# sch_design.net
KiCad netlist of a schematic drawn in EAGLE
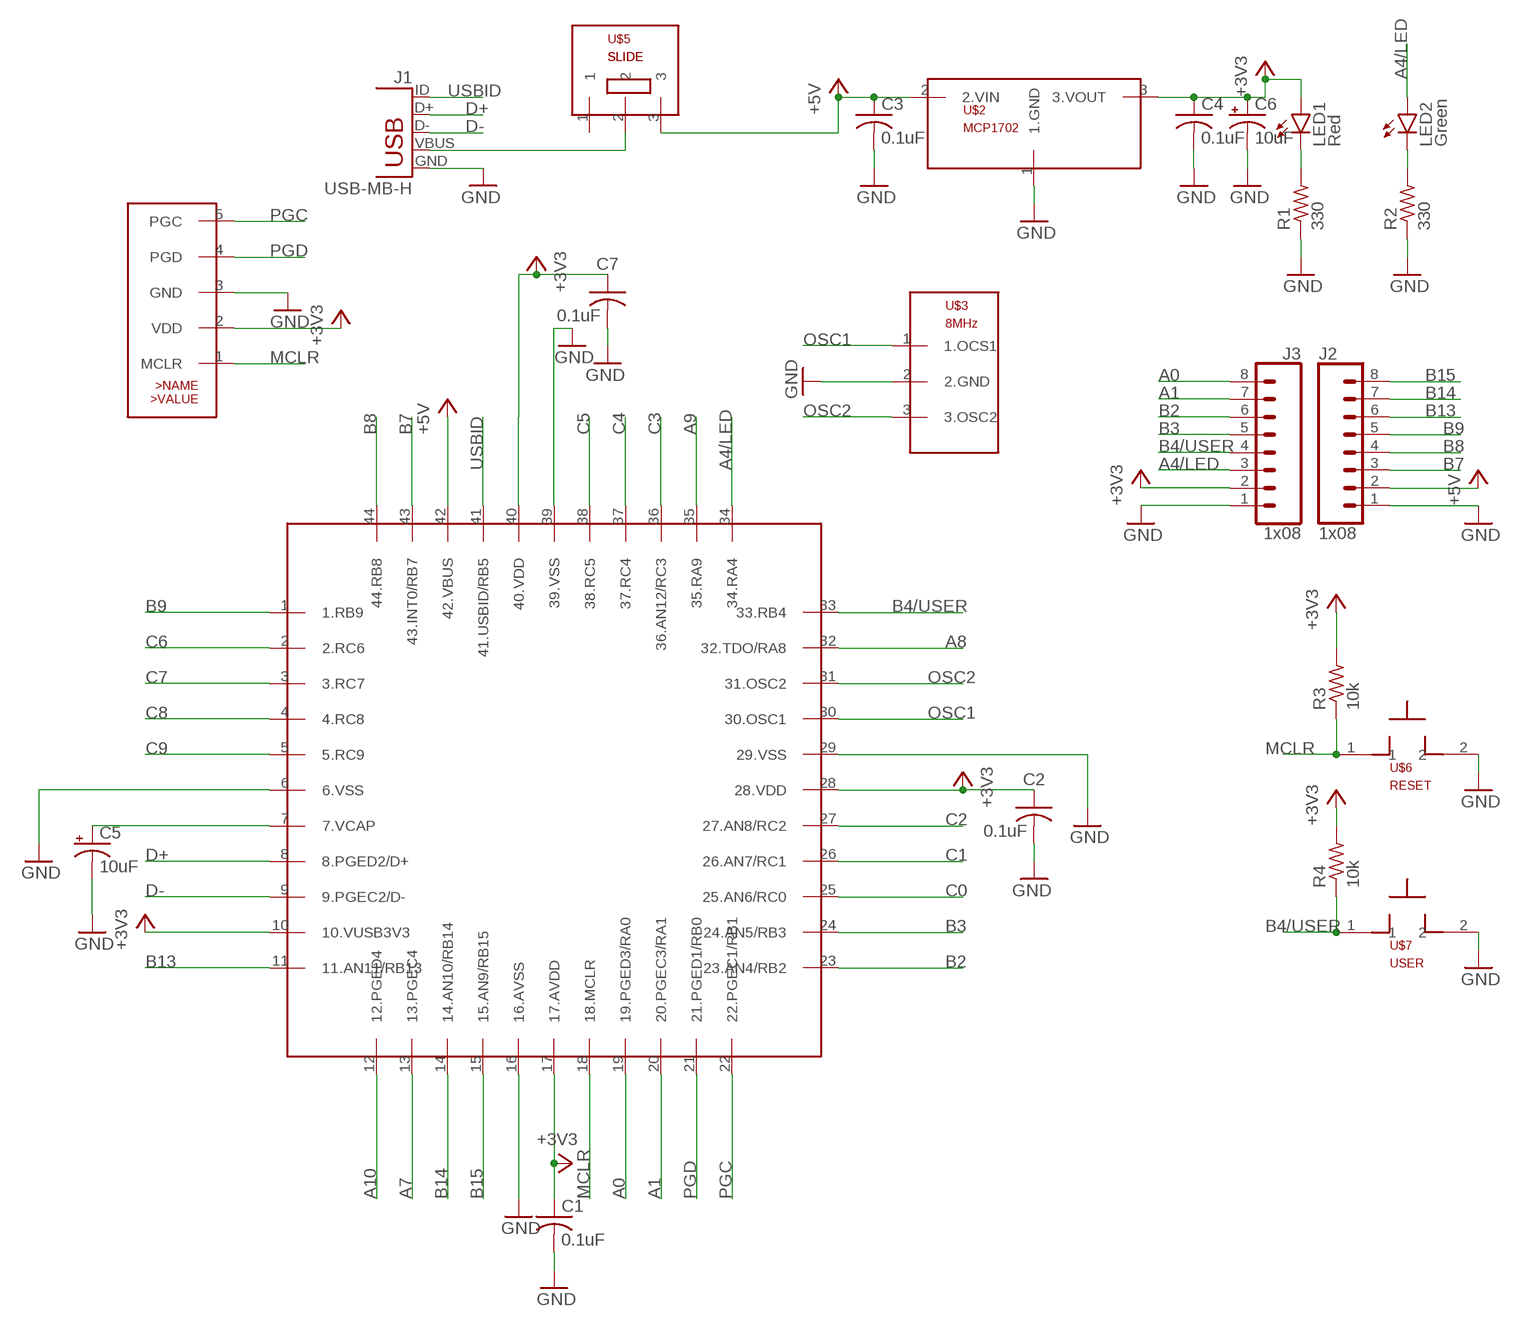
[diagram p0: schematic, sheet 1]

(export (version "E")
  (design (tool "Eeschema 10.0.6"))
  (components
    (comp (ref "C1")
      (value "0.1uF")
      (footprint "eagle-import:C025-025X050")
      (libsource (lib "eagle-import") (part "C-US025-025X050"))
    )
    (comp (ref "C2")
      (value "0.1uF")
      (footprint "eagle-import:C025-025X050")
      (libsource (lib "eagle-import") (part "C-US025-025X050"))
    )
    (comp (ref "C3")
      (value "0.1uF")
      (footprint "eagle-import:C025-025X050")
      (libsource (lib "eagle-import") (part "C-US025-025X050"))
    )
    (comp (ref "C4")
      (value "0.1uF")
      (footprint "eagle-import:C025-025X050")
      (libsource (lib "eagle-import") (part "C-US025-025X050"))
    )
    (comp (ref "C5")
      (value "10uF")
      (footprint "eagle-import:B45181B")
      (libsource (lib "eagle-import") (part "CPOL-USB45181B"))
    )
    (comp (ref "C6")
      (value "10uF")
      (footprint "eagle-import:B45181B")
      (libsource (lib "eagle-import") (part "CPOL-USB45181B"))
    )
    (comp (ref "C7")
      (value "0.1uF")
      (footprint "eagle-import:C025-025X050")
      (libsource (lib "eagle-import") (part "C-US025-025X050"))
    )
    (comp (ref "J1")
      (value "USB-MB-H")
      (footprint "eagle-import:USB-MB-H")
      (libsource (lib "eagle-import") (part "USB-MB-H"))
    )
    (comp (ref "J2")
      (value "1x08")
      (footprint "eagle-import:1X08")
      (libsource (lib "eagle-import") (part "CONN_08{dblquote}"))
    )
    (comp (ref "J3")
      (value "1x08")
      (footprint "eagle-import:1X08")
      (libsource (lib "eagle-import") (part "CONN_08{dblquote}"))
    )
    (comp (ref "LED1")
      (value "Red")
      (footprint "eagle-import:LED3MM")
      (libsource (lib "eagle-import") (part "LED3MM"))
    )
    (comp (ref "LED2")
      (value "Green")
      (footprint "eagle-import:LED3MM")
      (libsource (lib "eagle-import") (part "LED3MM"))
    )
    (comp (ref "R1")
      (value "330")
      (footprint "eagle-import:0207_10")
      (libsource (lib "eagle-import") (part "R-US_0207/10"))
    )
    (comp (ref "R2")
      (value "330")
      (footprint "eagle-import:0207_10")
      (libsource (lib "eagle-import") (part "R-US_0207/10"))
    )
    (comp (ref "R3")
      (value "10k")
      (footprint "eagle-import:0207_10")
      (libsource (lib "eagle-import") (part "R-US_0207/10"))
    )
    (comp (ref "R4")
      (value "10k")
      (footprint "eagle-import:0207_10")
      (libsource (lib "eagle-import") (part "R-US_0207/10"))
    )
    (comp (ref "U$2")
      (value "MCP1702")
      (footprint "eagle-import:TO92")
      (libsource (lib "eagle-import") (part "MCP1702"))
    )
    (comp (ref "U$3")
      (value "8MHz")
      (footprint "eagle-import:OSC")
      (libsource (lib "eagle-import") (part "OSC"))
    )
    (comp (ref "U$4")
      (value "PICKIT3")
      (footprint "eagle-import:1X05")
      (libsource (lib "eagle-import") (part "PICKIT3"))
    )
    (comp (ref "U$5")
      (value "SLIDE")
      (footprint "eagle-import:SLIDE")
      (libsource (lib "eagle-import") (part "SLIDE"))
    )
    (comp (ref "U$6")
      (value "RESET")
      (footprint "eagle-import:PB")
      (libsource (lib "eagle-import") (part "PB"))
    )
    (comp (ref "U$7")
      (value "USER")
      (footprint "eagle-import:PB")
      (libsource (lib "eagle-import") (part "PB"))
    )
    (comp (ref "U$8")
      (value "PIC32MX270F256D")
      (footprint "eagle-import:TQFP44")
      (libsource (lib "eagle-import") (part "PIC32MX270F256D"))
    )
  )
  (nets
    (net (code "1") (name "+3V3") (class "Default")
      (node (ref "C1") (pin "1") (pinfunction "1_1") (pintype "passive"))
      (node (ref "C2") (pin "1") (pinfunction "1_1") (pintype "passive"))
      (node (ref "C4") (pin "1") (pinfunction "1_1") (pintype "passive"))
      (node (ref "C6") (pin "+") (pinfunction "+_+") (pintype "passive"))
      (node (ref "C7") (pin "1") (pinfunction "1_1") (pintype "passive"))
      (node (ref "J3") (pin "2") (pinfunction "2_2") (pintype "passive"))
      (node (ref "LED1") (pin "A") (pinfunction "A_A") (pintype "passive"))
      (node (ref "R3") (pin "2") (pinfunction "2_2") (pintype "passive"))
      (node (ref "R4") (pin "2") (pinfunction "2_2") (pintype "passive"))
      (node (ref "U$2") (pin "3") (pinfunction "3.VOUT_3") (pintype "bidirectional"))
      (node (ref "U$4") (pin "2") (pinfunction "VDD_2") (pintype "bidirectional"))
      (node (ref "U$8") (pin "10") (pinfunction "10.VUSB3V3_10") (pintype "bidirectional"))
      (node (ref "U$8") (pin "17") (pinfunction "17.AVDD_17") (pintype "bidirectional"))
      (node (ref "U$8") (pin "28") (pinfunction "28.VDD_28") (pintype "bidirectional"))
      (node (ref "U$8") (pin "40") (pinfunction "40.VDD_40") (pintype "bidirectional"))
    )
    (net (code "2") (name "+5V") (class "Default")
      (node (ref "C3") (pin "1") (pinfunction "1_1") (pintype "passive"))
      (node (ref "J2") (pin "2") (pinfunction "2_2") (pintype "passive"))
      (node (ref "U$2") (pin "2") (pinfunction "2.VIN_2") (pintype "bidirectional"))
      (node (ref "U$5") (pin "3") (pinfunction "3_3") (pintype "bidirectional"))
      (node (ref "U$8") (pin "42") (pinfunction "42.VBUS_42") (pintype "bidirectional"))
    )
    (net (code "3") (name "/A0") (class "Default")
      (node (ref "J3") (pin "8") (pinfunction "8_8") (pintype "passive"))
      (node (ref "U$8") (pin "19") (pinfunction "19.PGED3/RA0_19") (pintype "bidirectional"))
    )
    (net (code "4") (name "/A1") (class "Default")
      (node (ref "J3") (pin "7") (pinfunction "7_7") (pintype "passive"))
      (node (ref "U$8") (pin "20") (pinfunction "20.PGEC3/RA1_20") (pintype "bidirectional"))
    )
    (net (code "5") (name "/A4{slash}LED") (class "Default")
      (node (ref "J3") (pin "3") (pinfunction "3_3") (pintype "passive"))
      (node (ref "LED2") (pin "A") (pinfunction "A_A") (pintype "passive"))
      (node (ref "U$8") (pin "34") (pinfunction "34.RA4_34") (pintype "bidirectional"))
    )
    (net (code "6") (name "/A7") (class "Default")
      (node (ref "U$8") (pin "13") (pinfunction "13.PGEC4_13") (pintype "bidirectional"))
    )
    (net (code "7") (name "/A8") (class "Default")
      (node (ref "U$8") (pin "32") (pinfunction "32.TDO/RA8_32") (pintype "bidirectional"))
    )
    (net (code "8") (name "/A9") (class "Default")
      (node (ref "U$8") (pin "35") (pinfunction "35.RA9_35") (pintype "bidirectional"))
    )
    (net (code "9") (name "/A10") (class "Default")
      (node (ref "U$8") (pin "12") (pinfunction "12.PGED4_12") (pintype "bidirectional"))
    )
    (net (code "10") (name "/B2") (class "Default")
      (node (ref "J3") (pin "6") (pinfunction "6_6") (pintype "passive"))
      (node (ref "U$8") (pin "23") (pinfunction "23.AN4/RB2_23") (pintype "bidirectional"))
    )
    (net (code "11") (name "/B3") (class "Default")
      (node (ref "J3") (pin "5") (pinfunction "5_5") (pintype "passive"))
      (node (ref "U$8") (pin "24") (pinfunction "24.AN5/RB3_24") (pintype "bidirectional"))
    )
    (net (code "12") (name "/B4{slash}USER") (class "Default")
      (node (ref "J3") (pin "4") (pinfunction "4_4") (pintype "passive"))
      (node (ref "R4") (pin "1") (pinfunction "1_1") (pintype "passive"))
      (node (ref "U$7") (pin "1") (pinfunction "1_1") (pintype "bidirectional"))
      (node (ref "U$8") (pin "33") (pinfunction "33.RB4_33") (pintype "bidirectional"))
    )
    (net (code "13") (name "/B7") (class "Default")
      (node (ref "J2") (pin "3") (pinfunction "3_3") (pintype "passive"))
      (node (ref "U$8") (pin "43") (pinfunction "43.INT0/RB7_43") (pintype "bidirectional"))
    )
    (net (code "14") (name "/B8") (class "Default")
      (node (ref "J2") (pin "4") (pinfunction "4_4") (pintype "passive"))
      (node (ref "U$8") (pin "44") (pinfunction "44.RB8_44") (pintype "bidirectional"))
    )
    (net (code "15") (name "/B9") (class "Default")
      (node (ref "J2") (pin "5") (pinfunction "5_5") (pintype "passive"))
      (node (ref "U$8") (pin "1") (pinfunction "1.RB9_1") (pintype "bidirectional"))
    )
    (net (code "16") (name "/B13") (class "Default")
      (node (ref "J2") (pin "6") (pinfunction "6_6") (pintype "passive"))
      (node (ref "U$8") (pin "11") (pinfunction "11.AN11/RB13_11") (pintype "bidirectional"))
    )
    (net (code "17") (name "/B14") (class "Default")
      (node (ref "J2") (pin "7") (pinfunction "7_7") (pintype "passive"))
      (node (ref "U$8") (pin "14") (pinfunction "14.AN10/RB14_14") (pintype "bidirectional"))
    )
    (net (code "18") (name "/B15") (class "Default")
      (node (ref "J2") (pin "8") (pinfunction "8_8") (pintype "passive"))
      (node (ref "U$8") (pin "15") (pinfunction "15.AN9/RB15_15") (pintype "bidirectional"))
    )
    (net (code "19") (name "/C0") (class "Default")
      (node (ref "U$8") (pin "25") (pinfunction "25.AN6/RC0_25") (pintype "bidirectional"))
    )
    (net (code "20") (name "/C1") (class "Default")
      (node (ref "U$8") (pin "26") (pinfunction "26.AN7/RC1_26") (pintype "bidirectional"))
    )
    (net (code "21") (name "/C2") (class "Default")
      (node (ref "U$8") (pin "27") (pinfunction "27.AN8/RC2_27") (pintype "bidirectional"))
    )
    (net (code "22") (name "/C3") (class "Default")
      (node (ref "U$8") (pin "36") (pinfunction "36.AN12/RC3_36") (pintype "bidirectional"))
    )
    (net (code "23") (name "/C4") (class "Default")
      (node (ref "U$8") (pin "37") (pinfunction "37.RC4_37") (pintype "bidirectional"))
    )
    (net (code "24") (name "/C5") (class "Default")
      (node (ref "U$8") (pin "38") (pinfunction "38.RC5_38") (pintype "bidirectional"))
    )
    (net (code "25") (name "/C6") (class "Default")
      (node (ref "U$8") (pin "2") (pinfunction "2.RC6_2") (pintype "bidirectional"))
    )
    (net (code "26") (name "/C7") (class "Default")
      (node (ref "U$8") (pin "3") (pinfunction "3.RC7_3") (pintype "bidirectional"))
    )
    (net (code "27") (name "/C8") (class "Default")
      (node (ref "U$8") (pin "4") (pinfunction "4.RC8_4") (pintype "bidirectional"))
    )
    (net (code "28") (name "/C9") (class "Default")
      (node (ref "U$8") (pin "5") (pinfunction "5.RC9_5") (pintype "bidirectional"))
    )
    (net (code "29") (name "/D+") (class "Default")
      (node (ref "J1") (pin "D+") (pinfunction "D+_D+") (pintype "bidirectional"))
      (node (ref "U$8") (pin "8") (pinfunction "8.PGED2/D+_8") (pintype "bidirectional"))
    )
    (net (code "30") (name "/D-") (class "Default")
      (node (ref "J1") (pin "D-") (pinfunction "D-_D-") (pintype "bidirectional"))
      (node (ref "U$8") (pin "9") (pinfunction "9.PGEC2/D-_9") (pintype "bidirectional"))
    )
    (net (code "31") (name "/MCLR") (class "Default")
      (node (ref "R3") (pin "1") (pinfunction "1_1") (pintype "passive"))
      (node (ref "U$4") (pin "1") (pinfunction "MCLR_1") (pintype "bidirectional"))
      (node (ref "U$6") (pin "1") (pinfunction "1_1") (pintype "bidirectional"))
      (node (ref "U$8") (pin "18") (pinfunction "18.MCLR_18") (pintype "bidirectional"))
    )
    (net (code "32") (name "/OSC1") (class "Default")
      (node (ref "U$3") (pin "1") (pinfunction "1.OCS1_1") (pintype "bidirectional"))
      (node (ref "U$8") (pin "30") (pinfunction "30.OSC1_30") (pintype "bidirectional"))
    )
    (net (code "33") (name "/OSC2") (class "Default")
      (node (ref "U$3") (pin "3") (pinfunction "3.OSC2_3") (pintype "bidirectional"))
      (node (ref "U$8") (pin "31") (pinfunction "31.OSC2_31") (pintype "bidirectional"))
    )
    (net (code "34") (name "/PGC") (class "Default")
      (node (ref "U$4") (pin "5") (pinfunction "PGC_5") (pintype "bidirectional"))
      (node (ref "U$8") (pin "22") (pinfunction "22.PGEC1/RB1_22") (pintype "bidirectional"))
    )
    (net (code "35") (name "/PGD") (class "Default")
      (node (ref "U$4") (pin "4") (pinfunction "PGD_4") (pintype "bidirectional"))
      (node (ref "U$8") (pin "21") (pinfunction "21.PGED1/RB0_21") (pintype "bidirectional"))
    )
    (net (code "36") (name "/USBID") (class "Default")
      (node (ref "J1") (pin "ID") (pinfunction "ID_ID") (pintype "bidirectional"))
      (node (ref "U$8") (pin "41") (pinfunction "41.USBID/RB5_41") (pintype "bidirectional"))
    )
    (net (code "37") (name "GND") (class "Default")
      (node (ref "C1") (pin "2") (pinfunction "2_2") (pintype "passive"))
      (node (ref "C2") (pin "2") (pinfunction "2_2") (pintype "passive"))
      (node (ref "C3") (pin "2") (pinfunction "2_2") (pintype "passive"))
      (node (ref "C4") (pin "2") (pinfunction "2_2") (pintype "passive"))
      (node (ref "C5") (pin "-") (pinfunction "-_-") (pintype "passive"))
      (node (ref "C6") (pin "-") (pinfunction "-_-") (pintype "passive"))
      (node (ref "C7") (pin "2") (pinfunction "2_2") (pintype "passive"))
      (node (ref "J1") (pin "GND") (pinfunction "GND_GND") (pintype "bidirectional"))
      (node (ref "J2") (pin "1") (pinfunction "1_1") (pintype "passive"))
      (node (ref "J3") (pin "1") (pinfunction "1_1") (pintype "passive"))
      (node (ref "R1") (pin "1") (pinfunction "1_1") (pintype "passive"))
      (node (ref "R2") (pin "1") (pinfunction "1_1") (pintype "passive"))
      (node (ref "U$2") (pin "1") (pinfunction "1.GND_1") (pintype "bidirectional"))
      (node (ref "U$3") (pin "2") (pinfunction "2.GND_2") (pintype "bidirectional"))
      (node (ref "U$4") (pin "3") (pinfunction "GND_3") (pintype "bidirectional"))
      (node (ref "U$6") (pin "2") (pinfunction "2_2") (pintype "bidirectional"))
      (node (ref "U$7") (pin "2") (pinfunction "2_2") (pintype "bidirectional"))
      (node (ref "U$8") (pin "16") (pinfunction "16.AVSS_16") (pintype "bidirectional"))
      (node (ref "U$8") (pin "29") (pinfunction "29.VSS_29") (pintype "bidirectional"))
      (node (ref "U$8") (pin "39") (pinfunction "39.VSS_39") (pintype "bidirectional"))
      (node (ref "U$8") (pin "6") (pinfunction "6.VSS_6") (pintype "bidirectional"))
    )
    (net (code "38") (name "Net-(J1-PadVBUS)") (class "Default")
      (node (ref "J1") (pin "VBUS") (pinfunction "VBUS_VBUS") (pintype "bidirectional"))
      (node (ref "U$5") (pin "2") (pinfunction "2_2") (pintype "bidirectional"))
    )
    (net (code "39") (name "Net-(LED1-C)") (class "Default")
      (node (ref "LED1") (pin "K") (pinfunction "C_K") (pintype "passive"))
      (node (ref "R1") (pin "2") (pinfunction "2_2") (pintype "passive"))
    )
    (net (code "40") (name "Net-(LED2-C)") (class "Default")
      (node (ref "LED2") (pin "K") (pinfunction "C_K") (pintype "passive"))
      (node (ref "R2") (pin "2") (pinfunction "2_2") (pintype "passive"))
    )
    (net (code "41") (name "Net-(U$8-7.VCAP)") (class "Default")
      (node (ref "C5") (pin "+") (pinfunction "+_+") (pintype "passive"))
      (node (ref "U$8") (pin "7") (pinfunction "7.VCAP_7") (pintype "bidirectional"))
    )
    (net (code "42") (name "unconnected-(U$5-Pad1)") (class "Default")
      (node (ref "U$5") (pin "1") (pinfunction "1_1") (pintype "bidirectional"))
    )
  )
)
